# linesensor.net
KiCad netlist of a schematic drawn in EAGLE
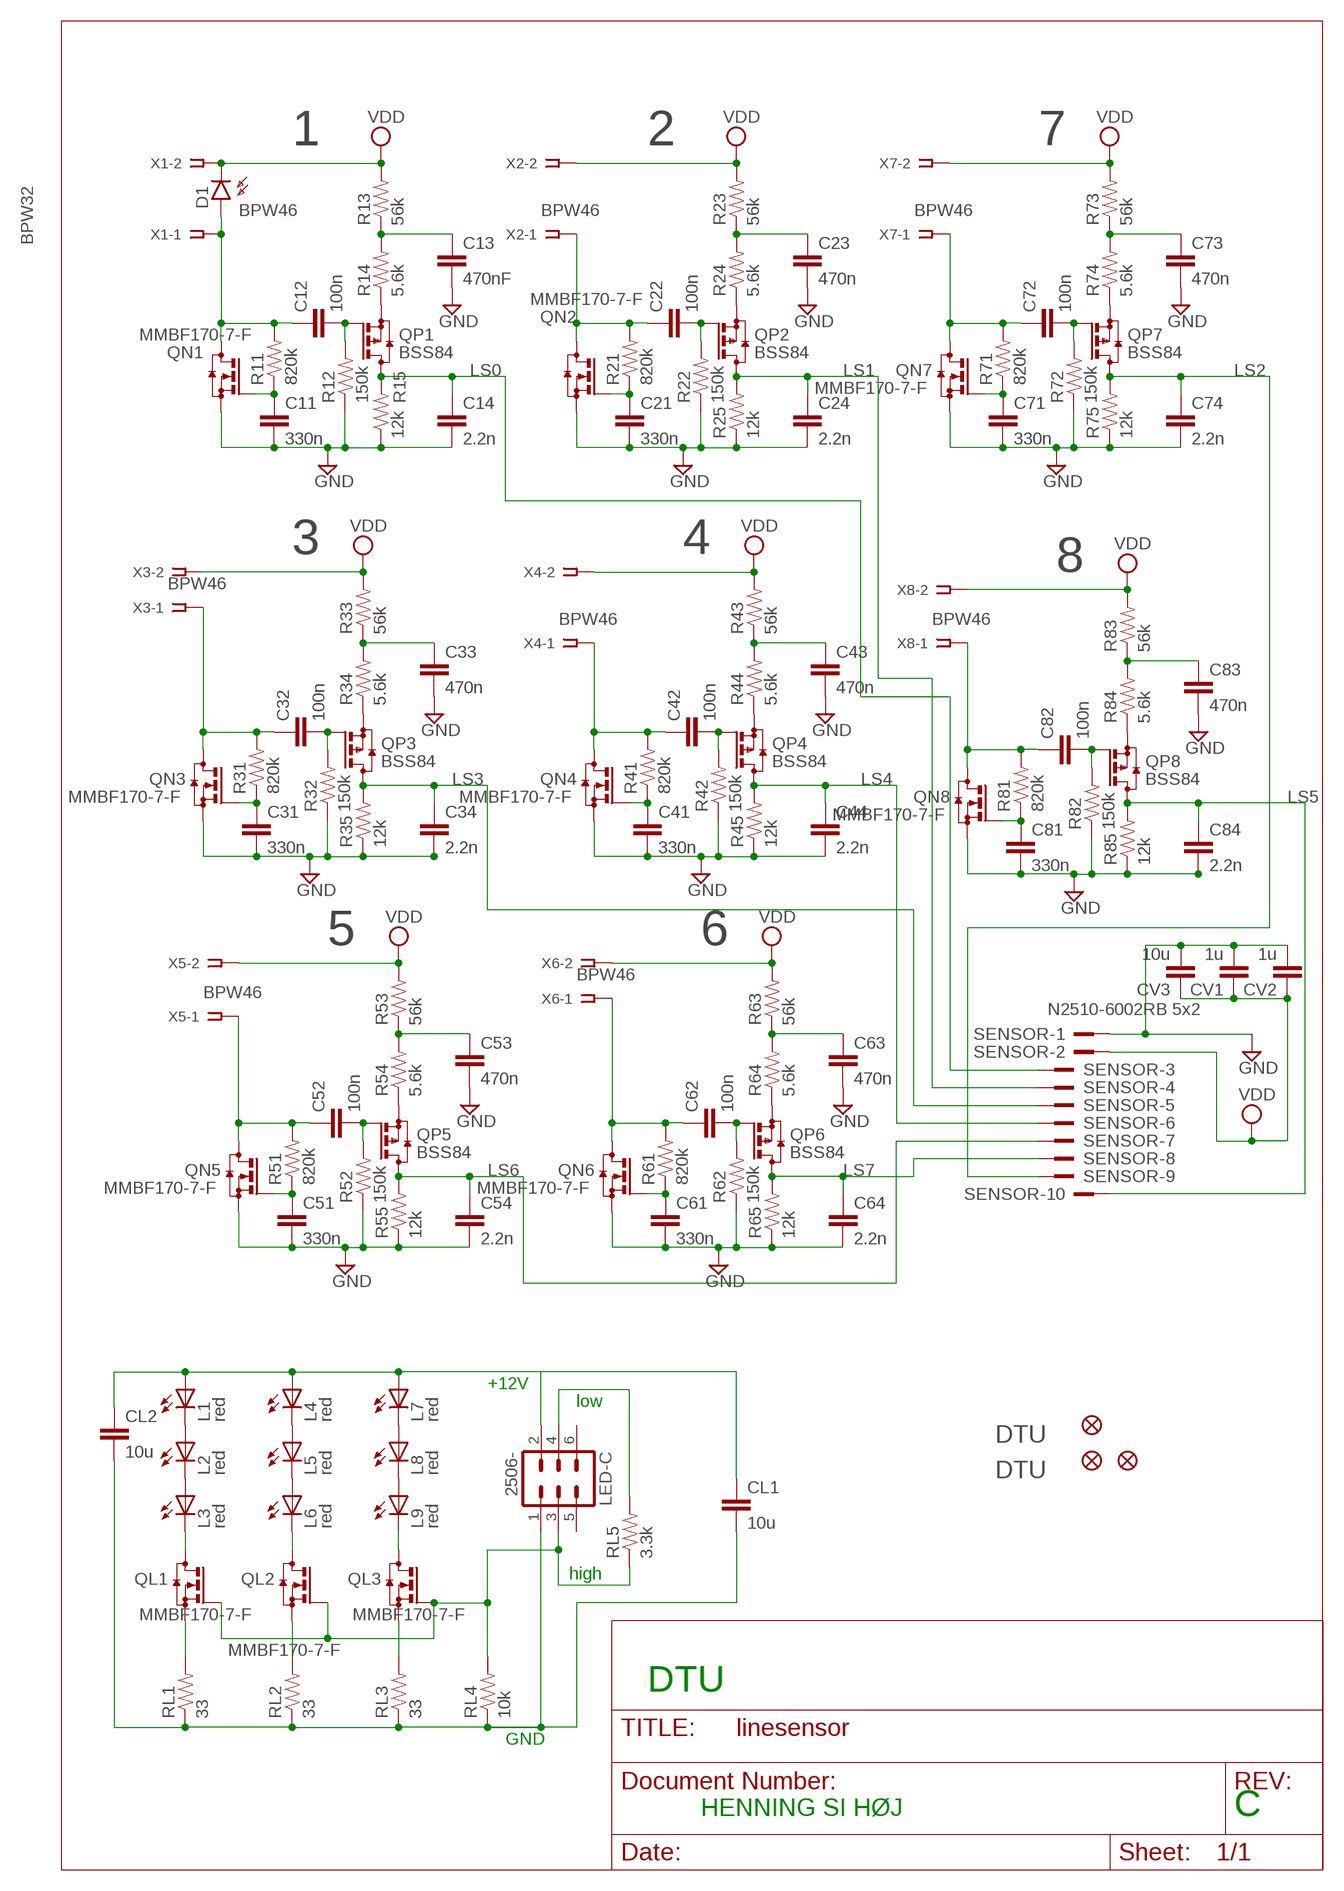
[diagram p0: schematic, sheet 1]

(export (version "E")
  (design (tool "Eeschema 10.0.6"))
  (components
    (comp (ref "C11")
      (value "330n")
      (footprint "eagle-import:0805")
      (libsource (lib "eagle-import") (part "CAP0805"))
    )
    (comp (ref "C12")
      (value "100n")
      (footprint "eagle-import:0805")
      (libsource (lib "eagle-import") (part "CAP0805"))
    )
    (comp (ref "C13")
      (value "470nF")
      (footprint "eagle-import:0805")
      (libsource (lib "eagle-import") (part "CAP0805"))
    )
    (comp (ref "C14")
      (value "2.2n")
      (footprint "eagle-import:0805")
      (libsource (lib "eagle-import") (part "CAP0805"))
    )
    (comp (ref "C21")
      (value "330n")
      (footprint "eagle-import:0805")
      (libsource (lib "eagle-import") (part "CAP0805"))
    )
    (comp (ref "C22")
      (value "100n")
      (footprint "eagle-import:0805")
      (libsource (lib "eagle-import") (part "CAP0805"))
    )
    (comp (ref "C23")
      (value "470n")
      (footprint "eagle-import:0805")
      (libsource (lib "eagle-import") (part "CAP0805"))
    )
    (comp (ref "C24")
      (value "2.2n")
      (footprint "eagle-import:0805")
      (libsource (lib "eagle-import") (part "CAP0805"))
    )
    (comp (ref "C31")
      (value "330n")
      (footprint "eagle-import:0805")
      (libsource (lib "eagle-import") (part "CAP0805"))
    )
    (comp (ref "C32")
      (value "100n")
      (footprint "eagle-import:0805")
      (libsource (lib "eagle-import") (part "CAP0805"))
    )
    (comp (ref "C33")
      (value "470n")
      (footprint "eagle-import:0805")
      (libsource (lib "eagle-import") (part "CAP0805"))
    )
    (comp (ref "C34")
      (value "2.2n")
      (footprint "eagle-import:0805")
      (libsource (lib "eagle-import") (part "CAP0805"))
    )
    (comp (ref "C41")
      (value "330n")
      (footprint "eagle-import:0805")
      (libsource (lib "eagle-import") (part "CAP0805"))
    )
    (comp (ref "C42")
      (value "100n")
      (footprint "eagle-import:0805")
      (libsource (lib "eagle-import") (part "CAP0805"))
    )
    (comp (ref "C43")
      (value "470n")
      (footprint "eagle-import:0805")
      (libsource (lib "eagle-import") (part "CAP0805"))
    )
    (comp (ref "C44")
      (value "2.2n")
      (footprint "eagle-import:0805")
      (libsource (lib "eagle-import") (part "CAP0805"))
    )
    (comp (ref "C51")
      (value "330n")
      (footprint "eagle-import:0805")
      (libsource (lib "eagle-import") (part "CAP0805"))
    )
    (comp (ref "C52")
      (value "100n")
      (footprint "eagle-import:0805")
      (libsource (lib "eagle-import") (part "CAP0805"))
    )
    (comp (ref "C53")
      (value "470n")
      (footprint "eagle-import:0805")
      (libsource (lib "eagle-import") (part "CAP0805"))
    )
    (comp (ref "C54")
      (value "2.2n")
      (footprint "eagle-import:0805")
      (libsource (lib "eagle-import") (part "CAP0805"))
    )
    (comp (ref "C61")
      (value "330n")
      (footprint "eagle-import:0805")
      (libsource (lib "eagle-import") (part "CAP0805"))
    )
    (comp (ref "C62")
      (value "100n")
      (footprint "eagle-import:0805")
      (libsource (lib "eagle-import") (part "CAP0805"))
    )
    (comp (ref "C63")
      (value "470n")
      (footprint "eagle-import:0805")
      (libsource (lib "eagle-import") (part "CAP0805"))
    )
    (comp (ref "C64")
      (value "2.2n")
      (footprint "eagle-import:0805")
      (libsource (lib "eagle-import") (part "CAP0805"))
    )
    (comp (ref "C71")
      (value "330n")
      (footprint "eagle-import:0805")
      (libsource (lib "eagle-import") (part "CAP0805"))
    )
    (comp (ref "C72")
      (value "100n")
      (footprint "eagle-import:0805")
      (libsource (lib "eagle-import") (part "CAP0805"))
    )
    (comp (ref "C73")
      (value "470n")
      (footprint "eagle-import:0805")
      (libsource (lib "eagle-import") (part "CAP0805"))
    )
    (comp (ref "C74")
      (value "2.2n")
      (footprint "eagle-import:0805")
      (libsource (lib "eagle-import") (part "CAP0805"))
    )
    (comp (ref "C81")
      (value "330n")
      (footprint "eagle-import:0805")
      (libsource (lib "eagle-import") (part "CAP0805"))
    )
    (comp (ref "C82")
      (value "100n")
      (footprint "eagle-import:0805")
      (libsource (lib "eagle-import") (part "CAP0805"))
    )
    (comp (ref "C83")
      (value "470n")
      (footprint "eagle-import:0805")
      (libsource (lib "eagle-import") (part "CAP0805"))
    )
    (comp (ref "C84")
      (value "2.2n")
      (footprint "eagle-import:0805")
      (libsource (lib "eagle-import") (part "CAP0805"))
    )
    (comp (ref "CL1")
      (value "10u")
      (footprint "eagle-import:1210")
      (libsource (lib "eagle-import") (part "CAP1210"))
    )
    (comp (ref "CL2")
      (value "10u")
      (footprint "eagle-import:1210")
      (libsource (lib "eagle-import") (part "CAP1210"))
    )
    (comp (ref "CV1")
      (value "1u")
      (footprint "eagle-import:0805")
      (libsource (lib "eagle-import") (part "CAP0805"))
    )
    (comp (ref "CV2")
      (value "1u")
      (footprint "eagle-import:0805")
      (libsource (lib "eagle-import") (part "CAP0805"))
    )
    (comp (ref "CV3")
      (value "10u")
      (footprint "eagle-import:1210")
      (libsource (lib "eagle-import") (part "CAP1210"))
    )
    (comp (ref "D1")
      (value "BPW32")
      (footprint "eagle-import:BPW32")
      (libsource (lib "eagle-import") (part "BPW32"))
    )
    (comp (ref "FD1")
      (value "FIDUCIAL1X2")
      (footprint "eagle-import:FIDUCIAL-1X2")
      (libsource (lib "eagle-import") (part "FIDUCIAL1X2"))
    )
    (comp (ref "FD2")
      (value "FIDUCIAL1X2")
      (footprint "eagle-import:FIDUCIAL-1X2")
      (libsource (lib "eagle-import") (part "FIDUCIAL1X2"))
    )
    (comp (ref "FD3")
      (value "FIDUCIAL1X2")
      (footprint "eagle-import:FIDUCIAL-1X2")
      (libsource (lib "eagle-import") (part "FIDUCIAL1X2"))
    )
    (comp (ref "L1")
      (value "red")
      (footprint "eagle-import:LED3MM")
      (libsource (lib "eagle-import") (part "LED3MM"))
    )
    (comp (ref "L2")
      (value "red")
      (footprint "eagle-import:LED3MM")
      (libsource (lib "eagle-import") (part "LED3MM"))
    )
    (comp (ref "L3")
      (value "red")
      (footprint "eagle-import:LED3MM")
      (libsource (lib "eagle-import") (part "LED3MM"))
    )
    (comp (ref "L4")
      (value "red")
      (footprint "eagle-import:LED3MM")
      (libsource (lib "eagle-import") (part "LED3MM"))
    )
    (comp (ref "L5")
      (value "red")
      (footprint "eagle-import:LED3MM")
      (libsource (lib "eagle-import") (part "LED3MM"))
    )
    (comp (ref "L6")
      (value "red")
      (footprint "eagle-import:LED3MM")
      (libsource (lib "eagle-import") (part "LED3MM"))
    )
    (comp (ref "L7")
      (value "red")
      (footprint "eagle-import:LED3MM")
      (libsource (lib "eagle-import") (part "LED3MM"))
    )
    (comp (ref "L8")
      (value "red")
      (footprint "eagle-import:LED3MM")
      (libsource (lib "eagle-import") (part "LED3MM"))
    )
    (comp (ref "L9")
      (value "red")
      (footprint "eagle-import:LED3MM")
      (libsource (lib "eagle-import") (part "LED3MM"))
    )
    (comp (ref "LED-C")
      (value "2506-")
      (footprint "eagle-import:PAK100_2500-06")
      (libsource (lib "eagle-import") (part "2506-"))
    )
    (comp (ref "QL1")
      (value "MMBF170-7-F")
      (footprint "eagle-import:SOT23")
      (libsource (lib "eagle-import") (part "BSS123"))
    )
    (comp (ref "QL2")
      (value "MMBF170-7-F")
      (footprint "eagle-import:SOT23")
      (libsource (lib "eagle-import") (part "BSS123"))
    )
    (comp (ref "QL3")
      (value "MMBF170-7-F")
      (footprint "eagle-import:SOT23")
      (libsource (lib "eagle-import") (part "BSS123"))
    )
    (comp (ref "QN1")
      (value "MMBF170-7-F")
      (footprint "eagle-import:SOT23")
      (libsource (lib "eagle-import") (part "BSS123"))
    )
    (comp (ref "QN2")
      (value "MMBF170-7-F")
      (footprint "eagle-import:SOT23")
      (libsource (lib "eagle-import") (part "BSS123"))
    )
    (comp (ref "QN3")
      (value "MMBF170-7-F")
      (footprint "eagle-import:SOT23")
      (libsource (lib "eagle-import") (part "BSS123"))
    )
    (comp (ref "QN4")
      (value "MMBF170-7-F")
      (footprint "eagle-import:SOT23")
      (libsource (lib "eagle-import") (part "BSS123"))
    )
    (comp (ref "QN5")
      (value "MMBF170-7-F")
      (footprint "eagle-import:SOT23")
      (libsource (lib "eagle-import") (part "BSS123"))
    )
    (comp (ref "QN6")
      (value "MMBF170-7-F")
      (footprint "eagle-import:SOT23")
      (libsource (lib "eagle-import") (part "BSS123"))
    )
    (comp (ref "QN7")
      (value "MMBF170-7-F")
      (footprint "eagle-import:SOT23")
      (libsource (lib "eagle-import") (part "BSS123"))
    )
    (comp (ref "QN8")
      (value "MMBF170-7-F")
      (footprint "eagle-import:SOT23")
      (libsource (lib "eagle-import") (part "BSS123"))
    )
    (comp (ref "QP1")
      (value "BSS84")
      (footprint "eagle-import:SOT23")
      (libsource (lib "eagle-import") (part "BSS84"))
    )
    (comp (ref "QP2")
      (value "BSS84")
      (footprint "eagle-import:SOT23")
      (libsource (lib "eagle-import") (part "BSS84"))
    )
    (comp (ref "QP3")
      (value "BSS84")
      (footprint "eagle-import:SOT23")
      (libsource (lib "eagle-import") (part "BSS84"))
    )
    (comp (ref "QP4")
      (value "BSS84")
      (footprint "eagle-import:SOT23")
      (libsource (lib "eagle-import") (part "BSS84"))
    )
    (comp (ref "QP5")
      (value "BSS84")
      (footprint "eagle-import:SOT23")
      (libsource (lib "eagle-import") (part "BSS84"))
    )
    (comp (ref "QP6")
      (value "BSS84")
      (footprint "eagle-import:SOT23")
      (libsource (lib "eagle-import") (part "BSS84"))
    )
    (comp (ref "QP7")
      (value "BSS84")
      (footprint "eagle-import:SOT23")
      (libsource (lib "eagle-import") (part "BSS84"))
    )
    (comp (ref "QP8")
      (value "BSS84")
      (footprint "eagle-import:SOT23")
      (libsource (lib "eagle-import") (part "BSS84"))
    )
    (comp (ref "R11")
      (value "820k")
      (footprint "eagle-import:0805")
      (libsource (lib "eagle-import") (part "RESISTOR0805-RES"))
    )
    (comp (ref "R12")
      (value "150k")
      (footprint "eagle-import:0805")
      (libsource (lib "eagle-import") (part "RESISTOR0805-RES"))
    )
    (comp (ref "R13")
      (value "56k")
      (footprint "eagle-import:0805")
      (libsource (lib "eagle-import") (part "RESISTOR0805-RES"))
    )
    (comp (ref "R14")
      (value "5.6k")
      (footprint "eagle-import:0805")
      (libsource (lib "eagle-import") (part "RESISTOR0805-RES"))
    )
    (comp (ref "R15")
      (value "12k")
      (footprint "eagle-import:0805")
      (libsource (lib "eagle-import") (part "RESISTOR0805-RES"))
    )
    (comp (ref "R21")
      (value "820k")
      (footprint "eagle-import:0805")
      (libsource (lib "eagle-import") (part "RESISTOR0805-RES"))
    )
    (comp (ref "R22")
      (value "150k")
      (footprint "eagle-import:0805")
      (libsource (lib "eagle-import") (part "RESISTOR0805-RES"))
    )
    (comp (ref "R23")
      (value "56k")
      (footprint "eagle-import:0805")
      (libsource (lib "eagle-import") (part "RESISTOR0805-RES"))
    )
    (comp (ref "R24")
      (value "5.6k")
      (footprint "eagle-import:0805")
      (libsource (lib "eagle-import") (part "RESISTOR0805-RES"))
    )
    (comp (ref "R25")
      (value "12k")
      (footprint "eagle-import:0805")
      (libsource (lib "eagle-import") (part "RESISTOR0805-RES"))
    )
    (comp (ref "R31")
      (value "820k")
      (footprint "eagle-import:0805")
      (libsource (lib "eagle-import") (part "RESISTOR0805-RES"))
    )
    (comp (ref "R32")
      (value "150k")
      (footprint "eagle-import:0805")
      (libsource (lib "eagle-import") (part "RESISTOR0805-RES"))
    )
    (comp (ref "R33")
      (value "56k")
      (footprint "eagle-import:0805")
      (libsource (lib "eagle-import") (part "RESISTOR0805-RES"))
    )
    (comp (ref "R34")
      (value "5.6k")
      (footprint "eagle-import:0805")
      (libsource (lib "eagle-import") (part "RESISTOR0805-RES"))
    )
    (comp (ref "R35")
      (value "12k")
      (footprint "eagle-import:0805")
      (libsource (lib "eagle-import") (part "RESISTOR0805-RES"))
    )
    (comp (ref "R41")
      (value "820k")
      (footprint "eagle-import:0805")
      (libsource (lib "eagle-import") (part "RESISTOR0805-RES"))
    )
    (comp (ref "R42")
      (value "150k")
      (footprint "eagle-import:0805")
      (libsource (lib "eagle-import") (part "RESISTOR0805-RES"))
    )
    (comp (ref "R43")
      (value "56k")
      (footprint "eagle-import:0805")
      (libsource (lib "eagle-import") (part "RESISTOR0805-RES"))
    )
    (comp (ref "R44")
      (value "5.6k")
      (footprint "eagle-import:0805")
      (libsource (lib "eagle-import") (part "RESISTOR0805-RES"))
    )
    (comp (ref "R45")
      (value "12k")
      (footprint "eagle-import:0805")
      (libsource (lib "eagle-import") (part "RESISTOR0805-RES"))
    )
    (comp (ref "R51")
      (value "820k")
      (footprint "eagle-import:0805")
      (libsource (lib "eagle-import") (part "RESISTOR0805-RES"))
    )
    (comp (ref "R52")
      (value "150k")
      (footprint "eagle-import:0805")
      (libsource (lib "eagle-import") (part "RESISTOR0805-RES"))
    )
    (comp (ref "R53")
      (value "56k")
      (footprint "eagle-import:0805")
      (libsource (lib "eagle-import") (part "RESISTOR0805-RES"))
    )
    (comp (ref "R54")
      (value "5.6k")
      (footprint "eagle-import:0805")
      (libsource (lib "eagle-import") (part "RESISTOR0805-RES"))
    )
    (comp (ref "R55")
      (value "12k")
      (footprint "eagle-import:0805")
      (libsource (lib "eagle-import") (part "RESISTOR0805-RES"))
    )
    (comp (ref "R61")
      (value "820k")
      (footprint "eagle-import:0805")
      (libsource (lib "eagle-import") (part "RESISTOR0805-RES"))
    )
    (comp (ref "R62")
      (value "150k")
      (footprint "eagle-import:0805")
      (libsource (lib "eagle-import") (part "RESISTOR0805-RES"))
    )
    (comp (ref "R63")
      (value "56k")
      (footprint "eagle-import:0805")
      (libsource (lib "eagle-import") (part "RESISTOR0805-RES"))
    )
    (comp (ref "R64")
      (value "5.6k")
      (footprint "eagle-import:0805")
      (libsource (lib "eagle-import") (part "RESISTOR0805-RES"))
    )
    (comp (ref "R65")
      (value "12k")
      (footprint "eagle-import:0805")
      (libsource (lib "eagle-import") (part "RESISTOR0805-RES"))
    )
    (comp (ref "R71")
      (value "820k")
      (footprint "eagle-import:0805")
      (libsource (lib "eagle-import") (part "RESISTOR0805-RES"))
    )
    (comp (ref "R72")
      (value "150k")
      (footprint "eagle-import:0805")
      (libsource (lib "eagle-import") (part "RESISTOR0805-RES"))
    )
    (comp (ref "R73")
      (value "56k")
      (footprint "eagle-import:0805")
      (libsource (lib "eagle-import") (part "RESISTOR0805-RES"))
    )
    (comp (ref "R74")
      (value "5.6k")
      (footprint "eagle-import:0805")
      (libsource (lib "eagle-import") (part "RESISTOR0805-RES"))
    )
    (comp (ref "R75")
      (value "12k")
      (footprint "eagle-import:0805")
      (libsource (lib "eagle-import") (part "RESISTOR0805-RES"))
    )
    (comp (ref "R81")
      (value "820k")
      (footprint "eagle-import:0805")
      (libsource (lib "eagle-import") (part "RESISTOR0805-RES"))
    )
    (comp (ref "R82")
      (value "150k")
      (footprint "eagle-import:0805")
      (libsource (lib "eagle-import") (part "RESISTOR0805-RES"))
    )
    (comp (ref "R83")
      (value "56k")
      (footprint "eagle-import:0805")
      (libsource (lib "eagle-import") (part "RESISTOR0805-RES"))
    )
    (comp (ref "R84")
      (value "5.6k")
      (footprint "eagle-import:0805")
      (libsource (lib "eagle-import") (part "RESISTOR0805-RES"))
    )
    (comp (ref "R85")
      (value "12k")
      (footprint "eagle-import:0805")
      (libsource (lib "eagle-import") (part "RESISTOR0805-RES"))
    )
    (comp (ref "RL1")
      (value "33")
      (footprint "eagle-import:0805")
      (libsource (lib "eagle-import") (part "RESISTOR0805-RES"))
    )
    (comp (ref "RL2")
      (value "33")
      (footprint "eagle-import:0805")
      (libsource (lib "eagle-import") (part "RESISTOR0805-RES"))
    )
    (comp (ref "RL3")
      (value "33")
      (footprint "eagle-import:0805")
      (libsource (lib "eagle-import") (part "RESISTOR0805-RES"))
    )
    (comp (ref "RL4")
      (value "10k")
      (footprint "eagle-import:0805")
      (libsource (lib "eagle-import") (part "RESISTOR0805-RES"))
    )
    (comp (ref "RL5")
      (value "3.3k")
      (footprint "eagle-import:0805")
      (libsource (lib "eagle-import") (part "RESISTOR0805-RES"))
    )
    (comp (ref "SENSOR")
      (value "N2510-6002RB 5x2")
      (footprint "eagle-import:PAK100_2500-10")
      (fields (field (name "MF") "3M") (field (name "MPN") "2510-6002UB"))
      (libsource (lib "eagle-import") (part "2510-"))
    )
    (comp (ref "U$1")
      (value "DTUSMALL-5MM")
      (footprint "eagle-import:DTU-SMALL-5MM")
      (libsource (lib "eagle-import") (part "DTUSMALL-5MM"))
    )
    (comp (ref "U$2")
      (value "DTULARGE")
      (footprint "eagle-import:DTU-LARGE")
      (libsource (lib "eagle-import") (part "DTULARGE"))
    )
    (comp (ref "X1")
      (value "BPW46")
      (footprint "eagle-import:SSW-102-02-S-S")
      (fields (field (name "MPN") "SSW-102-02-S-S"))
      (libsource (lib "eagle-import") (part "SSW-102-02-S-S"))
    )
    (comp (ref "X2")
      (value "BPW46")
      (footprint "eagle-import:SSW-102-02-S-S")
      (fields (field (name "MPN") "SSW-102-02-S-S"))
      (libsource (lib "eagle-import") (part "SSW-102-02-S-S"))
    )
    (comp (ref "X3")
      (value "BPW46")
      (footprint "eagle-import:SSW-102-02-S-S")
      (fields (field (name "MPN") "SSW-102-02-S-S"))
      (libsource (lib "eagle-import") (part "SSW-102-02-S-S"))
    )
    (comp (ref "X4")
      (value "BPW46")
      (footprint "eagle-import:SSW-102-02-S-S")
      (fields (field (name "MPN") "SSW-102-02-S-S"))
      (libsource (lib "eagle-import") (part "SSW-102-02-S-S"))
    )
    (comp (ref "X5")
      (value "BPW46")
      (footprint "eagle-import:SSW-102-02-S-S")
      (fields (field (name "MPN") "SSW-102-02-S-S"))
      (libsource (lib "eagle-import") (part "SSW-102-02-S-S"))
    )
    (comp (ref "X6")
      (value "BPW46")
      (footprint "eagle-import:SSW-102-02-S-S")
      (fields (field (name "MPN") "SSW-102-02-S-S"))
      (libsource (lib "eagle-import") (part "SSW-102-02-S-S"))
    )
    (comp (ref "X7")
      (value "BPW46")
      (footprint "eagle-import:SSW-102-02-S-S")
      (fields (field (name "MPN") "SSW-102-02-S-S"))
      (libsource (lib "eagle-import") (part "SSW-102-02-S-S"))
    )
    (comp (ref "X8")
      (value "BPW46")
      (footprint "eagle-import:SSW-102-02-S-S")
      (fields (field (name "MPN") "SSW-102-02-S-S"))
      (libsource (lib "eagle-import") (part "SSW-102-02-S-S"))
    )
  )
  (nets
    (net (code "1") (name "/LS0") (class "Default")
      (node (ref "C14") (pin "1") (pinfunction "1_1") (pintype "passive"))
      (node (ref "QP1") (pin "3") (pinfunction "D_3") (pintype "passive"))
      (node (ref "R15") (pin "2") (pinfunction "2_2") (pintype "passive"))
      (node (ref "SENSOR") (pin "3") (pinfunction "KL_3") (pintype "passive"))
    )
    (net (code "2") (name "/LS1") (class "Default")
      (node (ref "C24") (pin "1") (pinfunction "1_1") (pintype "passive"))
      (node (ref "QP2") (pin "3") (pinfunction "D_3") (pintype "passive"))
      (node (ref "R25") (pin "2") (pinfunction "2_2") (pintype "passive"))
      (node (ref "SENSOR") (pin "4") (pinfunction "KL_4") (pintype "passive"))
    )
    (net (code "3") (name "/LS2") (class "Default")
      (node (ref "C74") (pin "1") (pinfunction "1_1") (pintype "passive"))
      (node (ref "QP7") (pin "3") (pinfunction "D_3") (pintype "passive"))
      (node (ref "R75") (pin "2") (pinfunction "2_2") (pintype "passive"))
      (node (ref "SENSOR") (pin "9") (pinfunction "KL_9") (pintype "passive"))
    )
    (net (code "4") (name "/LS3") (class "Default")
      (node (ref "C34") (pin "1") (pinfunction "1_1") (pintype "passive"))
      (node (ref "QP3") (pin "3") (pinfunction "D_3") (pintype "passive"))
      (node (ref "R35") (pin "2") (pinfunction "2_2") (pintype "passive"))
      (node (ref "SENSOR") (pin "5") (pinfunction "KL_5") (pintype "passive"))
    )
    (net (code "5") (name "/LS4") (class "Default")
      (node (ref "C44") (pin "1") (pinfunction "1_1") (pintype "passive"))
      (node (ref "QP4") (pin "3") (pinfunction "D_3") (pintype "passive"))
      (node (ref "R45") (pin "2") (pinfunction "2_2") (pintype "passive"))
      (node (ref "SENSOR") (pin "6") (pinfunction "KL_6") (pintype "passive"))
    )
    (net (code "6") (name "/LS5") (class "Default")
      (node (ref "C84") (pin "1") (pinfunction "1_1") (pintype "passive"))
      (node (ref "QP8") (pin "3") (pinfunction "D_3") (pintype "passive"))
      (node (ref "R85") (pin "2") (pinfunction "2_2") (pintype "passive"))
      (node (ref "SENSOR") (pin "10") (pinfunction "KL_10") (pintype "passive"))
    )
    (net (code "7") (name "/LS6") (class "Default")
      (node (ref "C54") (pin "1") (pinfunction "1_1") (pintype "passive"))
      (node (ref "QP5") (pin "3") (pinfunction "D_3") (pintype "passive"))
      (node (ref "R55") (pin "2") (pinfunction "2_2") (pintype "passive"))
      (node (ref "SENSOR") (pin "7") (pinfunction "KL_7") (pintype "passive"))
    )
    (net (code "8") (name "/LS7") (class "Default")
      (node (ref "C64") (pin "1") (pinfunction "1_1") (pintype "passive"))
      (node (ref "QP6") (pin "3") (pinfunction "D_3") (pintype "passive"))
      (node (ref "R65") (pin "2") (pinfunction "2_2") (pintype "passive"))
      (node (ref "SENSOR") (pin "8") (pinfunction "KL_8") (pintype "passive"))
    )
    (net (code "9") (name "GND") (class "Default")
      (node (ref "C11") (pin "2") (pinfunction "2_2") (pintype "passive"))
      (node (ref "C13") (pin "2") (pinfunction "2_2") (pintype "passive"))
      (node (ref "C14") (pin "2") (pinfunction "2_2") (pintype "passive"))
      (node (ref "C21") (pin "2") (pinfunction "2_2") (pintype "passive"))
      (node (ref "C23") (pin "2") (pinfunction "2_2") (pintype "passive"))
      (node (ref "C24") (pin "2") (pinfunction "2_2") (pintype "passive"))
      (node (ref "C31") (pin "2") (pinfunction "2_2") (pintype "passive"))
      (node (ref "C33") (pin "2") (pinfunction "2_2") (pintype "passive"))
      (node (ref "C34") (pin "2") (pinfunction "2_2") (pintype "passive"))
      (node (ref "C41") (pin "2") (pinfunction "2_2") (pintype "passive"))
      (node (ref "C43") (pin "2") (pinfunction "2_2") (pintype "passive"))
      (node (ref "C44") (pin "2") (pinfunction "2_2") (pintype "passive"))
      (node (ref "C51") (pin "2") (pinfunction "2_2") (pintype "passive"))
      (node (ref "C53") (pin "2") (pinfunction "2_2") (pintype "passive"))
      (node (ref "C54") (pin "2") (pinfunction "2_2") (pintype "passive"))
      (node (ref "C61") (pin "2") (pinfunction "2_2") (pintype "passive"))
      (node (ref "C63") (pin "2") (pinfunction "2_2") (pintype "passive"))
      (node (ref "C64") (pin "2") (pinfunction "2_2") (pintype "passive"))
      (node (ref "C71") (pin "2") (pinfunction "2_2") (pintype "passive"))
      (node (ref "C73") (pin "2") (pinfunction "2_2") (pintype "passive"))
      (node (ref "C74") (pin "2") (pinfunction "2_2") (pintype "passive"))
      (node (ref "C81") (pin "2") (pinfunction "2_2") (pintype "passive"))
      (node (ref "C83") (pin "2") (pinfunction "2_2") (pintype "passive"))
      (node (ref "C84") (pin "2") (pinfunction "2_2") (pintype "passive"))
      (node (ref "CV1") (pin "2") (pinfunction "2_2") (pintype "passive"))
      (node (ref "CV2") (pin "2") (pinfunction "2_2") (pintype "passive"))
      (node (ref "CV3") (pin "2") (pinfunction "2_2") (pintype "passive"))
      (node (ref "QN1") (pin "2") (pinfunction "S_2") (pintype "passive"))
      (node (ref "QN2") (pin "2") (pinfunction "S_2") (pintype "passive"))
      (node (ref "QN3") (pin "2") (pinfunction "S_2") (pintype "passive"))
      (node (ref "QN4") (pin "2") (pinfunction "S_2") (pintype "passive"))
      (node (ref "QN5") (pin "2") (pinfunction "S_2") (pintype "passive"))
      (node (ref "QN6") (pin "2") (pinfunction "S_2") (pintype "passive"))
      (node (ref "QN7") (pin "2") (pinfunction "S_2") (pintype "passive"))
      (node (ref "QN8") (pin "2") (pinfunction "S_2") (pintype "passive"))
      (node (ref "R12") (pin "1") (pinfunction "1_1") (pintype "passive"))
      (node (ref "R15") (pin "1") (pinfunction "1_1") (pintype "passive"))
      (node (ref "R22") (pin "1") (pinfunction "1_1") (pintype "passive"))
      (node (ref "R25") (pin "1") (pinfunction "1_1") (pintype "passive"))
      (node (ref "R32") (pin "1") (pinfunction "1_1") (pintype "passive"))
      (node (ref "R35") (pin "1") (pinfunction "1_1") (pintype "passive"))
      (node (ref "R42") (pin "1") (pinfunction "1_1") (pintype "passive"))
      (node (ref "R45") (pin "1") (pinfunction "1_1") (pintype "passive"))
      (node (ref "R52") (pin "1") (pinfunction "1_1") (pintype "passive"))
      (node (ref "R55") (pin "1") (pinfunction "1_1") (pintype "passive"))
      (node (ref "R62") (pin "1") (pinfunction "1_1") (pintype "passive"))
      (node (ref "R65") (pin "1") (pinfunction "1_1") (pintype "passive"))
      (node (ref "R72") (pin "1") (pinfunction "1_1") (pintype "passive"))
      (node (ref "R75") (pin "1") (pinfunction "1_1") (pintype "passive"))
      (node (ref "R82") (pin "1") (pinfunction "1_1") (pintype "passive"))
      (node (ref "R85") (pin "1") (pinfunction "1_1") (pintype "passive"))
      (node (ref "SENSOR") (pin "1") (pinfunction "KL_1") (pintype "passive"))
    )
    (net (code "10") (name "Net-(C13-Pad1)") (class "Default")
      (node (ref "C13") (pin "1") (pinfunction "1_1") (pintype "passive"))
      (node (ref "R13") (pin "1") (pinfunction "1_1") (pintype "passive"))
      (node (ref "R14") (pin "2") (pinfunction "2_2") (pintype "passive"))
    )
    (net (code "11") (name "Net-(C23-Pad1)") (class "Default")
      (node (ref "C23") (pin "1") (pinfunction "1_1") (pintype "passive"))
      (node (ref "R23") (pin "1") (pinfunction "1_1") (pintype "passive"))
      (node (ref "R24") (pin "2") (pinfunction "2_2") (pintype "passive"))
    )
    (net (code "12") (name "Net-(C33-Pad1)") (class "Default")
      (node (ref "C33") (pin "1") (pinfunction "1_1") (pintype "passive"))
      (node (ref "R33") (pin "1") (pinfunction "1_1") (pintype "passive"))
      (node (ref "R34") (pin "2") (pinfunction "2_2") (pintype "passive"))
    )
    (net (code "13") (name "Net-(C43-Pad1)") (class "Default")
      (node (ref "C43") (pin "1") (pinfunction "1_1") (pintype "passive"))
      (node (ref "R43") (pin "1") (pinfunction "1_1") (pintype "passive"))
      (node (ref "R44") (pin "2") (pinfunction "2_2") (pintype "passive"))
    )
    (net (code "14") (name "Net-(C53-Pad1)") (class "Default")
      (node (ref "C53") (pin "1") (pinfunction "1_1") (pintype "passive"))
      (node (ref "R53") (pin "1") (pinfunction "1_1") (pintype "passive"))
      (node (ref "R54") (pin "2") (pinfunction "2_2") (pintype "passive"))
    )
    (net (code "15") (name "Net-(C63-Pad1)") (class "Default")
      (node (ref "C63") (pin "1") (pinfunction "1_1") (pintype "passive"))
      (node (ref "R63") (pin "1") (pinfunction "1_1") (pintype "passive"))
      (node (ref "R64") (pin "2") (pinfunction "2_2") (pintype "passive"))
    )
    (net (code "16") (name "Net-(C73-Pad1)") (class "Default")
      (node (ref "C73") (pin "1") (pinfunction "1_1") (pintype "passive"))
      (node (ref "R73") (pin "1") (pinfunction "1_1") (pintype "passive"))
      (node (ref "R74") (pin "2") (pinfunction "2_2") (pintype "passive"))
    )
    (net (code "17") (name "Net-(C83-Pad1)") (class "Default")
      (node (ref "C83") (pin "1") (pinfunction "1_1") (pintype "passive"))
      (node (ref "R83") (pin "1") (pinfunction "1_1") (pintype "passive"))
      (node (ref "R84") (pin "2") (pinfunction "2_2") (pintype "passive"))
    )
    (net (code "18") (name "Net-(CL1-Pad1)") (class "Default")
      (node (ref "CL1") (pin "1") (pinfunction "1_1") (pintype "passive"))
      (node (ref "CL2") (pin "1") (pinfunction "1_1") (pintype "passive"))
      (node (ref "L1") (pin "A") (pinfunction "A_A") (pintype "passive"))
      (node (ref "L4") (pin "A") (pinfunction "A_A") (pintype "passive"))
      (node (ref "L7") (pin "A") (pinfunction "A_A") (pintype "passive"))
      (node (ref "LED-C") (pin "2") (pinfunction "2_2") (pintype "passive"))
    )
    (net (code "19") (name "Net-(CL1-Pad2)") (class "Default")
      (node (ref "CL1") (pin "2") (pinfunction "2_2") (pintype "passive"))
      (node (ref "CL2") (pin "2") (pinfunction "2_2") (pintype "passive"))
      (node (ref "LED-C") (pin "1") (pinfunction "1_1") (pintype "passive"))
      (node (ref "RL1") (pin "1") (pinfunction "1_1") (pintype "passive"))
      (node (ref "RL2") (pin "1") (pinfunction "1_1") (pintype "passive"))
      (node (ref "RL3") (pin "1") (pinfunction "1_1") (pintype "passive"))
      (node (ref "RL4") (pin "1") (pinfunction "1_1") (pintype "passive"))
    )
    (net (code "20") (name "Net-(L1-C)") (class "Default")
      (node (ref "L1") (pin "K") (pinfunction "C_K") (pintype "passive"))
      (node (ref "L2") (pin "A") (pinfunction "A_A") (pintype "passive"))
    )
    (net (code "21") (name "Net-(L2-C)") (class "Default")
      (node (ref "L2") (pin "K") (pinfunction "C_K") (pintype "passive"))
      (node (ref "L3") (pin "A") (pinfunction "A_A") (pintype "passive"))
    )
    (net (code "22") (name "Net-(L3-C)") (class "Default")
      (node (ref "L3") (pin "K") (pinfunction "C_K") (pintype "passive"))
      (node (ref "QL1") (pin "3") (pinfunction "D_3") (pintype "passive"))
    )
    (net (code "23") (name "Net-(L4-C)") (class "Default")
      (node (ref "L4") (pin "K") (pinfunction "C_K") (pintype "passive"))
      (node (ref "L5") (pin "A") (pinfunction "A_A") (pintype "passive"))
    )
    (net (code "24") (name "Net-(L5-C)") (class "Default")
      (node (ref "L5") (pin "K") (pinfunction "C_K") (pintype "passive"))
      (node (ref "L6") (pin "A") (pinfunction "A_A") (pintype "passive"))
    )
    (net (code "25") (name "Net-(L6-C)") (class "Default")
      (node (ref "L6") (pin "K") (pinfunction "C_K") (pintype "passive"))
      (node (ref "QL2") (pin "3") (pinfunction "D_3") (pintype "passive"))
    )
    (net (code "26") (name "Net-(L7-C)") (class "Default")
      (node (ref "L7") (pin "K") (pinfunction "C_K") (pintype "passive"))
      (node (ref "L8") (pin "A") (pinfunction "A_A") (pintype "passive"))
    )
    (net (code "27") (name "Net-(L8-C)") (class "Default")
      (node (ref "L8") (pin "K") (pinfunction "C_K") (pintype "passive"))
      (node (ref "L9") (pin "A") (pinfunction "A_A") (pintype "passive"))
    )
    (net (code "28") (name "Net-(L9-C)") (class "Default")
      (node (ref "L9") (pin "K") (pinfunction "C_K") (pintype "passive"))
      (node (ref "QL3") (pin "3") (pinfunction "D_3") (pintype "passive"))
    )
    (net (code "29") (name "Net-(LED-C-Pad4)") (class "Default")
      (node (ref "LED-C") (pin "4") (pinfunction "4_4") (pintype "passive"))
      (node (ref "RL5") (pin "2") (pinfunction "2_2") (pintype "passive"))
    )
    (net (code "30") (name "Net-(QL1-G)") (class "Default")
      (node (ref "LED-C") (pin "3") (pinfunction "3_3") (pintype "passive"))
      (node (ref "QL1") (pin "1") (pinfunction "G_1") (pintype "passive"))
      (node (ref "QL2") (pin "1") (pinfunction "G_1") (pintype "passive"))
      (node (ref "QL3") (pin "1") (pinfunction "G_1") (pintype "passive"))
      (node (ref "RL4") (pin "2") (pinfunction "2_2") (pintype "passive"))
      (node (ref "RL5") (pin "1") (pinfunction "1_1") (pintype "passive"))
    )
    (net (code "31") (name "Net-(QL1-S)") (class "Default")
      (node (ref "QL1") (pin "2") (pinfunction "S_2") (pintype "passive"))
      (node (ref "RL1") (pin "2") (pinfunction "2_2") (pintype "passive"))
    )
    (net (code "32") (name "Net-(QL2-S)") (class "Default")
      (node (ref "QL2") (pin "2") (pinfunction "S_2") (pintype "passive"))
      (node (ref "RL2") (pin "2") (pinfunction "2_2") (pintype "passive"))
    )
    (net (code "33") (name "Net-(QL3-S)") (class "Default")
      (node (ref "QL3") (pin "2") (pinfunction "S_2") (pintype "passive"))
      (node (ref "RL3") (pin "2") (pinfunction "2_2") (pintype "passive"))
    )
    (net (code "34") (name "Net-(QN1-D)") (class "Default")
      (node (ref "C12") (pin "1") (pinfunction "1_1") (pintype "passive"))
      (node (ref "D1") (pin "A") (pinfunction "A_A") (pintype "passive"))
      (node (ref "QN1") (pin "3") (pinfunction "D_3") (pintype "passive"))
      (node (ref "R11") (pin "2") (pinfunction "2_2") (pintype "passive"))
      (node (ref "X1") (pin "1") (pinfunction "1_1") (pintype "passive"))
    )
    (net (code "35") (name "Net-(QN1-G)") (class "Default")
      (node (ref "C11") (pin "1") (pinfunction "1_1") (pintype "passive"))
      (node (ref "QN1") (pin "1") (pinfunction "G_1") (pintype "passive"))
      (node (ref "R11") (pin "1") (pinfunction "1_1") (pintype "passive"))
    )
    (net (code "36") (name "Net-(QN2-D)") (class "Default")
      (node (ref "C22") (pin "1") (pinfunction "1_1") (pintype "passive"))
      (node (ref "QN2") (pin "3") (pinfunction "D_3") (pintype "passive"))
      (node (ref "R21") (pin "2") (pinfunction "2_2") (pintype "passive"))
      (node (ref "X2") (pin "1") (pinfunction "1_1") (pintype "passive"))
    )
    (net (code "37") (name "Net-(QN2-G)") (class "Default")
      (node (ref "C21") (pin "1") (pinfunction "1_1") (pintype "passive"))
      (node (ref "QN2") (pin "1") (pinfunction "G_1") (pintype "passive"))
      (node (ref "R21") (pin "1") (pinfunction "1_1") (pintype "passive"))
    )
    (net (code "38") (name "Net-(QN3-D)") (class "Default")
      (node (ref "C32") (pin "1") (pinfunction "1_1") (pintype "passive"))
      (node (ref "QN3") (pin "3") (pinfunction "D_3") (pintype "passive"))
      (node (ref "R31") (pin "2") (pinfunction "2_2") (pintype "passive"))
      (node (ref "X3") (pin "1") (pinfunction "1_1") (pintype "passive"))
    )
    (net (code "39") (name "Net-(QN3-G)") (class "Default")
      (node (ref "C31") (pin "1") (pinfunction "1_1") (pintype "passive"))
      (node (ref "QN3") (pin "1") (pinfunction "G_1") (pintype "passive"))
      (node (ref "R31") (pin "1") (pinfunction "1_1") (pintype "passive"))
    )
    (net (code "40") (name "Net-(QN4-D)") (class "Default")
      (node (ref "C42") (pin "1") (pinfunction "1_1") (pintype "passive"))
      (node (ref "QN4") (pin "3") (pinfunction "D_3") (pintype "passive"))
      (node (ref "R41") (pin "2") (pinfunction "2_2") (pintype "passive"))
      (node (ref "X4") (pin "1") (pinfunction "1_1") (pintype "passive"))
    )
    (net (code "41") (name "Net-(QN4-G)") (class "Default")
      (node (ref "C41") (pin "1") (pinfunction "1_1") (pintype "passive"))
      (node (ref "QN4") (pin "1") (pinfunction "G_1") (pintype "passive"))
      (node (ref "R41") (pin "1") (pinfunction "1_1") (pintype "passive"))
    )
    (net (code "42") (name "Net-(QN5-D)") (class "Default")
      (node (ref "C52") (pin "1") (pinfunction "1_1") (pintype "passive"))
      (node (ref "QN5") (pin "3") (pinfunction "D_3") (pintype "passive"))
      (node (ref "R51") (pin "2") (pinfunction "2_2") (pintype "passive"))
      (node (ref "X5") (pin "1") (pinfunction "1_1") (pintype "passive"))
    )
    (net (code "43") (name "Net-(QN5-G)") (class "Default")
      (node (ref "C51") (pin "1") (pinfunction "1_1") (pintype "passive"))
      (node (ref "QN5") (pin "1") (pinfunction "G_1") (pintype "passive"))
      (node (ref "R51") (pin "1") (pinfunction "1_1") (pintype "passive"))
    )
    (net (code "44") (name "Net-(QN6-D)") (class "Default")
      (node (ref "C62") (pin "1") (pinfunction "1_1") (pintype "passive"))
      (node (ref "QN6") (pin "3") (pinfunction "D_3") (pintype "passive"))
      (node (ref "R61") (pin "2") (pinfunction "2_2") (pintype "passive"))
      (node (ref "X6") (pin "1") (pinfunction "1_1") (pintype "passive"))
    )
    (net (code "45") (name "Net-(QN6-G)") (class "Default")
      (node (ref "C61") (pin "1") (pinfunction "1_1") (pintype "passive"))
      (node (ref "QN6") (pin "1") (pinfunction "G_1") (pintype "passive"))
      (node (ref "R61") (pin "1") (pinfunction "1_1") (pintype "passive"))
    )
    (net (code "46") (name "Net-(QN7-D)") (class "Default")
      (node (ref "C72") (pin "1") (pinfunction "1_1") (pintype "passive"))
      (node (ref "QN7") (pin "3") (pinfunction "D_3") (pintype "passive"))
      (node (ref "R71") (pin "2") (pinfunction "2_2") (pintype "passive"))
      (node (ref "X7") (pin "1") (pinfunction "1_1") (pintype "passive"))
    )
    (net (code "47") (name "Net-(QN7-G)") (class "Default")
      (node (ref "C71") (pin "1") (pinfunction "1_1") (pintype "passive"))
      (node (ref "QN7") (pin "1") (pinfunction "G_1") (pintype "passive"))
      (node (ref "R71") (pin "1") (pinfunction "1_1") (pintype "passive"))
    )
    (net (code "48") (name "Net-(QN8-D)") (class "Default")
      (node (ref "C82") (pin "1") (pinfunction "1_1") (pintype "passive"))
      (node (ref "QN8") (pin "3") (pinfunction "D_3") (pintype "passive"))
      (node (ref "R81") (pin "2") (pinfunction "2_2") (pintype "passive"))
      (node (ref "X8") (pin "1") (pinfunction "1_1") (pintype "passive"))
    )
    (net (code "49") (name "Net-(QN8-G)") (class "Default")
      (node (ref "C81") (pin "1") (pinfunction "1_1") (pintype "passive"))
      (node (ref "QN8") (pin "1") (pinfunction "G_1") (pintype "passive"))
      (node (ref "R81") (pin "1") (pinfunction "1_1") (pintype "passive"))
    )
    (net (code "50") (name "Net-(QP1-G)") (class "Default")
      (node (ref "C12") (pin "2") (pinfunction "2_2") (pintype "passive"))
      (node (ref "QP1") (pin "1") (pinfunction "G_1") (pintype "passive"))
      (node (ref "R12") (pin "2") (pinfunction "2_2") (pintype "passive"))
    )
    (net (code "51") (name "Net-(QP1-S)") (class "Default")
      (node (ref "QP1") (pin "2") (pinfunction "S_2") (pintype "passive"))
      (node (ref "R14") (pin "1") (pinfunction "1_1") (pintype "passive"))
    )
    (net (code "52") (name "Net-(QP2-G)") (class "Default")
      (node (ref "C22") (pin "2") (pinfunction "2_2") (pintype "passive"))
      (node (ref "QP2") (pin "1") (pinfunction "G_1") (pintype "passive"))
      (node (ref "R22") (pin "2") (pinfunction "2_2") (pintype "passive"))
    )
    (net (code "53") (name "Net-(QP2-S)") (class "Default")
      (node (ref "QP2") (pin "2") (pinfunction "S_2") (pintype "passive"))
      (node (ref "R24") (pin "1") (pinfunction "1_1") (pintype "passive"))
    )
    (net (code "54") (name "Net-(QP3-G)") (class "Default")
      (node (ref "C32") (pin "2") (pinfunction "2_2") (pintype "passive"))
      (node (ref "QP3") (pin "1") (pinfunction "G_1") (pintype "passive"))
      (node (ref "R32") (pin "2") (pinfunction "2_2") (pintype "passive"))
    )
    (net (code "55") (name "Net-(QP3-S)") (class "Default")
      (node (ref "QP3") (pin "2") (pinfunction "S_2") (pintype "passive"))
      (node (ref "R34") (pin "1") (pinfunction "1_1") (pintype "passive"))
    )
    (net (code "56") (name "Net-(QP4-G)") (class "Default")
      (node (ref "C42") (pin "2") (pinfunction "2_2") (pintype "passive"))
      (node (ref "QP4") (pin "1") (pinfunction "G_1") (pintype "passive"))
      (node (ref "R42") (pin "2") (pinfunction "2_2") (pintype "passive"))
    )
    (net (code "57") (name "Net-(QP4-S)") (class "Default")
      (node (ref "QP4") (pin "2") (pinfunction "S_2") (pintype "passive"))
      (node (ref "R44") (pin "1") (pinfunction "1_1") (pintype "passive"))
    )
    (net (code "58") (name "Net-(QP5-G)") (class "Default")
      (node (ref "C52") (pin "2") (pinfunction "2_2") (pintype "passive"))
      (node (ref "QP5") (pin "1") (pinfunction "G_1") (pintype "passive"))
      (node (ref "R52") (pin "2") (pinfunction "2_2") (pintype "passive"))
    )
    (net (code "59") (name "Net-(QP5-S)") (class "Default")
      (node (ref "QP5") (pin "2") (pinfunction "S_2") (pintype "passive"))
      (node (ref "R54") (pin "1") (pinfunction "1_1") (pintype "passive"))
    )
    (net (code "60") (name "Net-(QP6-G)") (class "Default")
      (node (ref "C62") (pin "2") (pinfunction "2_2") (pintype "passive"))
      (node (ref "QP6") (pin "1") (pinfunction "G_1") (pintype "passive"))
      (node (ref "R62") (pin "2") (pinfunction "2_2") (pintype "passive"))
    )
    (net (code "61") (name "Net-(QP6-S)") (class "Default")
      (node (ref "QP6") (pin "2") (pinfunction "S_2") (pintype "passive"))
      (node (ref "R64") (pin "1") (pinfunction "1_1") (pintype "passive"))
    )
    (net (code "62") (name "Net-(QP7-G)") (class "Default")
      (node (ref "C72") (pin "2") (pinfunction "2_2") (pintype "passive"))
      (node (ref "QP7") (pin "1") (pinfunction "G_1") (pintype "passive"))
      (node (ref "R72") (pin "2") (pinfunction "2_2") (pintype "passive"))
    )
    (net (code "63") (name "Net-(QP7-S)") (class "Default")
      (node (ref "QP7") (pin "2") (pinfunction "S_2") (pintype "passive"))
      (node (ref "R74") (pin "1") (pinfunction "1_1") (pintype "passive"))
    )
    (net (code "64") (name "Net-(QP8-G)") (class "Default")
      (node (ref "C82") (pin "2") (pinfunction "2_2") (pintype "passive"))
      (node (ref "QP8") (pin "1") (pinfunction "G_1") (pintype "passive"))
      (node (ref "R82") (pin "2") (pinfunction "2_2") (pintype "passive"))
    )
    (net (code "65") (name "Net-(QP8-S)") (class "Default")
      (node (ref "QP8") (pin "2") (pinfunction "S_2") (pintype "passive"))
      (node (ref "R84") (pin "1") (pinfunction "1_1") (pintype "passive"))
    )
    (net (code "66") (name "VDD") (class "Default")
      (node (ref "CV1") (pin "1") (pinfunction "1_1") (pintype "passive"))
      (node (ref "CV2") (pin "1") (pinfunction "1_1") (pintype "passive"))
      (node (ref "CV3") (pin "1") (pinfunction "1_1") (pintype "passive"))
      (node (ref "D1") (pin "K") (pinfunction "C_K") (pintype "passive"))
      (node (ref "R13") (pin "2") (pinfunction "2_2") (pintype "passive"))
      (node (ref "R23") (pin "2") (pinfunction "2_2") (pintype "passive"))
      (node (ref "R33") (pin "2") (pinfunction "2_2") (pintype "passive"))
      (node (ref "R43") (pin "2") (pinfunction "2_2") (pintype "passive"))
      (node (ref "R53") (pin "2") (pinfunction "2_2") (pintype "passive"))
      (node (ref "R63") (pin "2") (pinfunction "2_2") (pintype "passive"))
      (node (ref "R73") (pin "2") (pinfunction "2_2") (pintype "passive"))
      (node (ref "R83") (pin "2") (pinfunction "2_2") (pintype "passive"))
      (node (ref "SENSOR") (pin "2") (pinfunction "KL_2") (pintype "passive"))
      (node (ref "X1") (pin "2") (pinfunction "1_2") (pintype "passive"))
      (node (ref "X2") (pin "2") (pinfunction "1_2") (pintype "passive"))
      (node (ref "X3") (pin "2") (pinfunction "1_2") (pintype "passive"))
      (node (ref "X4") (pin "2") (pinfunction "1_2") (pintype "passive"))
      (node (ref "X5") (pin "2") (pinfunction "1_2") (pintype "passive"))
      (node (ref "X6") (pin "2") (pinfunction "1_2") (pintype "passive"))
      (node (ref "X7") (pin "2") (pinfunction "1_2") (pintype "passive"))
      (node (ref "X8") (pin "2") (pinfunction "1_2") (pintype "passive"))
    )
    (net (code "67") (name "unconnected-(LED-C-Pad5)") (class "Default")
      (node (ref "LED-C") (pin "5") (pinfunction "5_5") (pintype "passive"))
    )
    (net (code "68") (name "unconnected-(LED-C-Pad6)") (class "Default")
      (node (ref "LED-C") (pin "6") (pinfunction "6_6") (pintype "passive"))
    )
  )
)
